# EasyEDA_schematic.net
KiCad netlist of a schematic drawn in EasyEDA
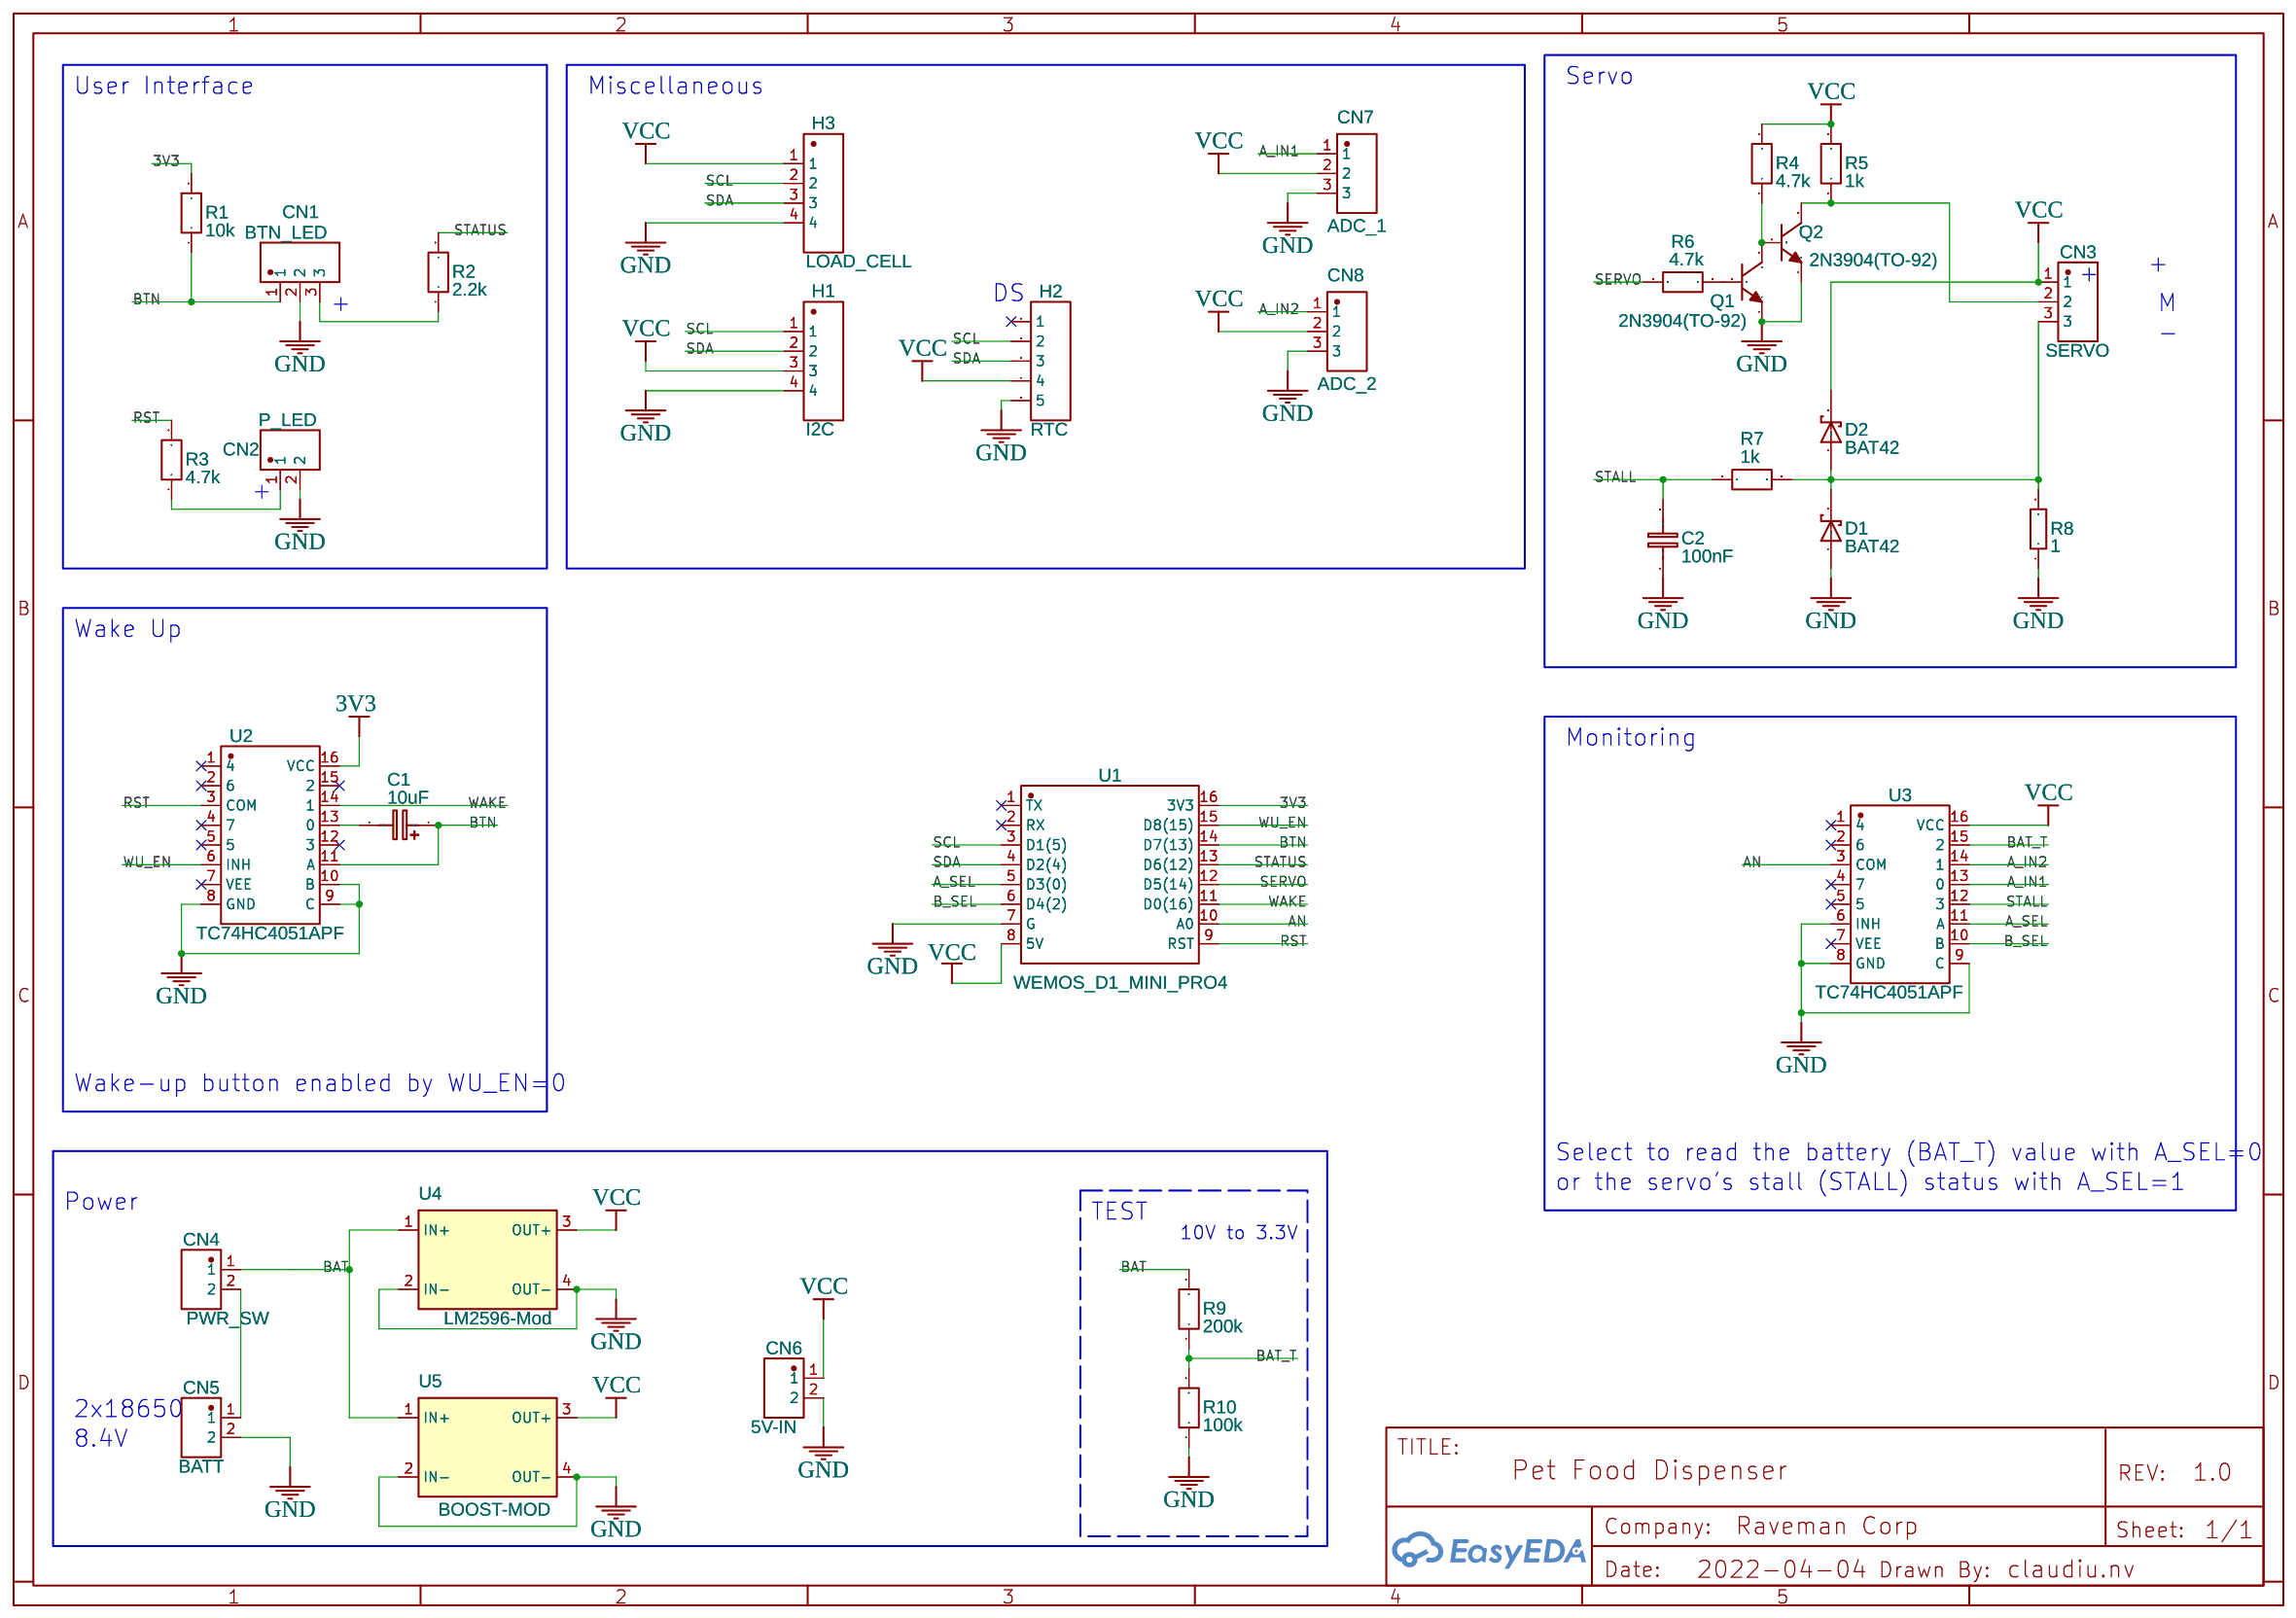
[diagram p0: schematic sheet]

(export (version "E")
  (design (tool "Eeschema 10.0.6"))
  (components
    (comp (ref "C1") (value "10uF") (libsource (lib "") (part "CE_TH_D3.0×F1.5_EU")))
    (comp (ref "C2") (value "100nF") (libsource (lib "") (part "C_RAD-0.1_EU")))
    (comp (ref "CN1")
      (value "BTN_LED")
      (fields (field (name "BOM_Manufacturer Part") "38006293") (field (name "BOM_Supplier Part") "C587424"))
      (libsource (lib "") (part "38006293_1"))
    )
    (comp (ref "CN2")
      (value "P_LED")
      (fields
        (field (name "BOM_Manufacturer Part") "1718560002")
        (field (name "BOM_Supplier Part") "C564997")
      )
      (libsource (lib "") (part "1718560002_1"))
    )
    (comp (ref "CN3")
      (value "SERVO")
      (fields (field (name "BOM_Manufacturer Part") "38006293") (field (name "BOM_Supplier Part") "C587424"))
      (libsource (lib "") (part "38006293"))
    )
    (comp (ref "CN4")
      (value "PWR_SW")
      (fields
        (field (name "BOM_Manufacturer Part") "1718560002")
        (field (name "BOM_Supplier Part") "C564997")
      )
      (libsource (lib "") (part "1718560002"))
    )
    (comp (ref "CN5")
      (value "BATT")
      (fields
        (field (name "BOM_Manufacturer Part") "1718560002")
        (field (name "BOM_Supplier Part") "C564997")
      )
      (libsource (lib "") (part "1718560002"))
    )
    (comp (ref "CN6")
      (value "5V-IN")
      (fields
        (field (name "BOM_Manufacturer Part") "1718560002")
        (field (name "BOM_Supplier Part") "C564997")
      )
      (libsource (lib "") (part "1718560002"))
    )
    (comp (ref "CN7")
      (value "ADC_1")
      (fields (field (name "BOM_Manufacturer Part") "38006293") (field (name "BOM_Supplier Part") "C587424"))
      (libsource (lib "") (part "38006293"))
    )
    (comp (ref "CN8")
      (value "ADC_2")
      (fields (field (name "BOM_Manufacturer Part") "38006293") (field (name "BOM_Supplier Part") "C587424"))
      (libsource (lib "") (part "38006293"))
    )
    (comp (ref "D1") (value "BAT42") (libsource (lib "") (part "1N5817-TP")))
    (comp (ref "D2") (value "BAT42") (libsource (lib "") (part "1N5817-TP")))
    (comp (ref "H1") (value "I2C") (libsource (lib "") (part "HEADER 4P 2.54MM")))
    (comp (ref "H2")
      (value "RTC")
      (fields (field (name "BOM_Supplier Part") "C50950"))
      (libsource (lib "") (part "HDR-F-2.54_1x5"))
    )
    (comp (ref "H3") (value "LOAD_CELL") (libsource (lib "") (part "HEADER 4P 2.54MM")))
    (comp (ref "Q1")
      (value "2N3904(TO-92)")
      (fields (field (name "BOM_Manufacturer Part") "2N3904") (field (name "BOM_Supplier Part") "C118538"))
      (libsource (lib "") (part "2N3904(TO-92)"))
    )
    (comp (ref "Q2")
      (value "2N3904(TO-92)")
      (fields (field (name "BOM_Manufacturer Part") "2N3904") (field (name "BOM_Supplier Part") "C118538"))
      (libsource (lib "") (part "2N3904(TO-92)"))
    )
    (comp (ref "R1") (value "10k") (libsource (lib "") (part "R_0603_EU")))
    (comp (ref "R2") (value "2.2k") (libsource (lib "") (part "R_0603_EU")))
    (comp (ref "R3") (value "4.7k") (libsource (lib "") (part "R_AXIAL-0.5_EU_1")))
    (comp (ref "R4") (value "4.7k") (libsource (lib "") (part "R_AXIAL-0.5_EU_1")))
    (comp (ref "R5") (value "1k") (libsource (lib "") (part "R_0603_EU")))
    (comp (ref "R6") (value "4.7k") (libsource (lib "") (part "R_0603_EU_1")))
    (comp (ref "R7") (value "1k") (libsource (lib "") (part "R_AXIAL-0.5_EU")))
    (comp (ref "R8")
      (value "1")
      (fields (field (name "BOM_Manufacturer Part") "CR-L5W1ΩJ") (field (name "BOM_Supplier Part") "C216404"))
      (libsource (lib "") (part "CR-L5W1ΩJ"))
    )
    (comp (ref "R9") (value "200k") (libsource (lib "") (part "R_AXIAL-0.5_EU_1")))
    (comp (ref "R10") (value "100k") (libsource (lib "") (part "R_AXIAL-0.5_EU_1")))
    (comp (ref "U1")
      (value "WEMOS_D1_MINI_PRO4")
      (fields
        (field (name "BOM_Manufacturer Part") "Wemos_D1_mini_Pro4")
        (field (name "BOM_Supplier Part") "C2837266")
      )
      (libsource (lib "") (part "WEMOS_D1_MINI_PRO4"))
    )
    (comp (ref "U2")
      (value "TC74HC4051APF")
      (fields (field (name "BOM_Supplier Part") "C1545945"))
      (libsource (lib "") (part "TC74HC4051APF"))
    )
    (comp (ref "U3")
      (value "TC74HC4051APF")
      (fields (field (name "BOM_Supplier Part") "C1545945"))
      (libsource (lib "") (part "TC74HC4051APF"))
    )
    (comp (ref "U4") (value "LM2596-Mod") (libsource (lib "") (part "LM2596-Mod")))
    (comp (ref "U5") (value "BOOST-MOD") (libsource (lib "") (part "BOOST-MOD")))
  )
  (nets
    (net (code "1") (name "/AN") (class "Default")
      (node (ref "U1") (pin "10") (pinfunction "A0_10") (pintype "unspecified"))
      (node (ref "U3") (pin "3") (pinfunction "COM_3") (pintype "unspecified"))
    )
    (net (code "2") (name "/A_IN1") (class "Default")
      (node (ref "CN7") (pin "1") (pinfunction "1_1") (pintype "unspecified"))
      (node (ref "U3") (pin "13") (pinfunction "0_13") (pintype "unspecified"))
    )
    (net (code "3") (name "/A_IN2") (class "Default")
      (node (ref "CN8") (pin "1") (pinfunction "1_1") (pintype "unspecified"))
      (node (ref "U3") (pin "14") (pinfunction "1_14") (pintype "unspecified"))
    )
    (net (code "4") (name "/A_SEL") (class "Default")
      (node (ref "U1") (pin "5") (pinfunction "D3(0)_5") (pintype "unspecified"))
      (node (ref "U3") (pin "11") (pinfunction "A_11") (pintype "unspecified"))
    )
    (net (code "5") (name "/BAT") (class "Default")
      (node (ref "CN4") (pin "1") (pinfunction "1_1") (pintype "unspecified"))
      (node (ref "R9") (pin "2") (pinfunction "2_2") (pintype "unspecified"))
      (node (ref "U4") (pin "1") (pinfunction "IN+_1") (pintype "passive"))
      (node (ref "U5") (pin "1") (pinfunction "IN+_1") (pintype "passive"))
    )
    (net (code "6") (name "/BAT_T") (class "Default")
      (node (ref "R10") (pin "2") (pinfunction "2_2") (pintype "unspecified"))
      (node (ref "R9") (pin "1") (pinfunction "1_1") (pintype "unspecified"))
      (node (ref "U3") (pin "15") (pinfunction "2_15") (pintype "unspecified"))
    )
    (net (code "7") (name "/BTN") (class "Default")
      (node (ref "C1") (pin "1") (pinfunction "1_1") (pintype "unspecified"))
      (node (ref "CN1") (pin "1") (pinfunction "1_1") (pintype "unspecified"))
      (node (ref "R1") (pin "1") (pinfunction "1_1") (pintype "unspecified"))
      (node (ref "U1") (pin "14") (pinfunction "D7(13)_14") (pintype "unspecified"))
      (node (ref "U2") (pin "11") (pinfunction "A_11") (pintype "unspecified"))
    )
    (net (code "8") (name "/B_SEL") (class "Default")
      (node (ref "U1") (pin "6") (pinfunction "D4(2)_6") (pintype "unspecified"))
      (node (ref "U3") (pin "10") (pinfunction "B_10") (pintype "unspecified"))
    )
    (net (code "9") (name "/RST") (class "Default")
      (node (ref "R3") (pin "2") (pinfunction "2_2") (pintype "unspecified"))
      (node (ref "U1") (pin "9") (pinfunction "RST_9") (pintype "unspecified"))
      (node (ref "U2") (pin "3") (pinfunction "COM_3") (pintype "unspecified"))
    )
    (net (code "10") (name "/SCL") (class "Default")
      (node (ref "H1") (pin "1") (pinfunction "1_1") (pintype "unspecified"))
      (node (ref "H2") (pin "2") (pinfunction "2_2") (pintype "unspecified"))
      (node (ref "H3") (pin "2") (pinfunction "2_2") (pintype "unspecified"))
      (node (ref "U1") (pin "3") (pinfunction "D1(5)_3") (pintype "unspecified"))
    )
    (net (code "11") (name "/SDA") (class "Default")
      (node (ref "H1") (pin "2") (pinfunction "2_2") (pintype "unspecified"))
      (node (ref "H2") (pin "3") (pinfunction "3_3") (pintype "unspecified"))
      (node (ref "H3") (pin "3") (pinfunction "3_3") (pintype "unspecified"))
      (node (ref "U1") (pin "4") (pinfunction "D2(4)_4") (pintype "unspecified"))
    )
    (net (code "12") (name "/SERVO") (class "Default")
      (node (ref "R6") (pin "1") (pinfunction "1_1") (pintype "unspecified"))
      (node (ref "U1") (pin "12") (pinfunction "D5(14)_12") (pintype "unspecified"))
    )
    (net (code "13") (name "/STALL") (class "Default")
      (node (ref "C2") (pin "2") (pinfunction "2_2") (pintype "unspecified"))
      (node (ref "R7") (pin "1") (pinfunction "1_1") (pintype "unspecified"))
      (node (ref "U3") (pin "12") (pinfunction "3_12") (pintype "unspecified"))
    )
    (net (code "14") (name "/STATUS") (class "Default")
      (node (ref "R2") (pin "2") (pinfunction "2_2") (pintype "unspecified"))
      (node (ref "U1") (pin "13") (pinfunction "D6(12)_13") (pintype "unspecified"))
    )
    (net (code "15") (name "/WAKE") (class "Default")
      (node (ref "U1") (pin "11") (pinfunction "D0(16)_11") (pintype "unspecified"))
      (node (ref "U2") (pin "14") (pinfunction "1_14") (pintype "unspecified"))
    )
    (net (code "16") (name "/WU_EN") (class "Default")
      (node (ref "U1") (pin "15") (pinfunction "D8(15)_15") (pintype "unspecified"))
      (node (ref "U2") (pin "6") (pinfunction "INH_6") (pintype "unspecified"))
    )
    (net (code "17") (name "3V3") (class "Default")
      (node (ref "R1") (pin "2") (pinfunction "2_2") (pintype "unspecified"))
      (node (ref "U1") (pin "16") (pinfunction "3V3_16") (pintype "unspecified"))
      (node (ref "U2") (pin "16") (pinfunction "VCC_16") (pintype "unspecified"))
    )
    (net (code "18") (name "GND") (class "Default")
      (node (ref "C2") (pin "1") (pinfunction "1_1") (pintype "unspecified"))
      (node (ref "CN1") (pin "2") (pinfunction "2_2") (pintype "unspecified"))
      (node (ref "CN2") (pin "2") (pinfunction "2_2") (pintype "unspecified"))
      (node (ref "CN5") (pin "2") (pinfunction "2_2") (pintype "unspecified"))
      (node (ref "CN6") (pin "2") (pinfunction "2_2") (pintype "unspecified"))
      (node (ref "CN7") (pin "3") (pinfunction "3_3") (pintype "unspecified"))
      (node (ref "CN8") (pin "3") (pinfunction "3_3") (pintype "unspecified"))
      (node (ref "D1") (pin "A") (pinfunction "A_A") (pintype "bidirectional"))
      (node (ref "H1") (pin "4") (pinfunction "4_4") (pintype "unspecified"))
      (node (ref "H2") (pin "5") (pinfunction "5_5") (pintype "unspecified"))
      (node (ref "H3") (pin "4") (pinfunction "4_4") (pintype "unspecified"))
      (node (ref "Q1") (pin "1") (pinfunction "E_1") (pintype "unspecified"))
      (node (ref "Q2") (pin "1") (pinfunction "E_1") (pintype "unspecified"))
      (node (ref "R10") (pin "1") (pinfunction "1_1") (pintype "unspecified"))
      (node (ref "R8") (pin "1") (pinfunction "1_1") (pintype "unspecified"))
      (node (ref "U1") (pin "7") (pinfunction "G_7") (pintype "unspecified"))
      (node (ref "U2") (pin "10") (pinfunction "B_10") (pintype "unspecified"))
      (node (ref "U2") (pin "8") (pinfunction "GND_8") (pintype "unspecified"))
      (node (ref "U2") (pin "9") (pinfunction "C_9") (pintype "unspecified"))
      (node (ref "U3") (pin "6") (pinfunction "INH_6") (pintype "unspecified"))
      (node (ref "U3") (pin "8") (pinfunction "GND_8") (pintype "unspecified"))
      (node (ref "U3") (pin "9") (pinfunction "C_9") (pintype "unspecified"))
      (node (ref "U4") (pin "2") (pinfunction "IN-_2") (pintype "passive"))
      (node (ref "U4") (pin "4") (pinfunction "OUT-_4") (pintype "passive"))
      (node (ref "U5") (pin "2") (pinfunction "IN-_2") (pintype "passive"))
      (node (ref "U5") (pin "4") (pinfunction "OUT-_4") (pintype "passive"))
    )
    (net (code "19") (name "Net-(CN1-Pad3)") (class "Default")
      (node (ref "CN1") (pin "3") (pinfunction "3_3") (pintype "unspecified"))
      (node (ref "R2") (pin "1") (pinfunction "1_1") (pintype "unspecified"))
    )
    (net (code "20") (name "Net-(CN2-Pad1)") (class "Default")
      (node (ref "CN2") (pin "1") (pinfunction "1_1") (pintype "unspecified"))
      (node (ref "R3") (pin "1") (pinfunction "1_1") (pintype "unspecified"))
    )
    (net (code "21") (name "Net-(CN3-Pad3)") (class "Default")
      (node (ref "CN3") (pin "3") (pinfunction "3_3") (pintype "unspecified"))
      (node (ref "D1") (pin "C") (pinfunction "C_C") (pintype "bidirectional"))
      (node (ref "D2") (pin "A") (pinfunction "A_A") (pintype "bidirectional"))
      (node (ref "R7") (pin "2") (pinfunction "2_2") (pintype "unspecified"))
      (node (ref "R8") (pin "2") (pinfunction "2_2") (pintype "unspecified"))
    )
    (net (code "22") (name "Net-(CN4-Pad2)") (class "Default")
      (node (ref "CN4") (pin "2") (pinfunction "2_2") (pintype "unspecified"))
      (node (ref "CN5") (pin "1") (pinfunction "1_1") (pintype "unspecified"))
    )
    (net (code "23") (name "Net-(Q1-B)") (class "Default")
      (node (ref "Q1") (pin "2") (pinfunction "B_2") (pintype "unspecified"))
      (node (ref "R6") (pin "2") (pinfunction "2_2") (pintype "unspecified"))
    )
    (net (code "24") (name "Net-(Q1-C)") (class "Default")
      (node (ref "Q1") (pin "3") (pinfunction "C_3") (pintype "unspecified"))
      (node (ref "Q2") (pin "2") (pinfunction "B_2") (pintype "unspecified"))
      (node (ref "R4") (pin "1") (pinfunction "1_1") (pintype "unspecified"))
    )
    (net (code "25") (name "Net-(Q2-C)") (class "Default")
      (node (ref "CN3") (pin "2") (pinfunction "2_2") (pintype "unspecified"))
      (node (ref "Q2") (pin "3") (pinfunction "C_3") (pintype "unspecified"))
      (node (ref "R5") (pin "1") (pinfunction "1_1") (pintype "unspecified"))
    )
    (net (code "26") (name "Net-(U2-0)") (class "Default")
      (node (ref "C1") (pin "2") (pinfunction "2_2") (pintype "unspecified"))
      (node (ref "U2") (pin "13") (pinfunction "0_13") (pintype "unspecified"))
    )
    (net (code "27") (name "VCC") (class "Default")
      (node (ref "CN3") (pin "1") (pinfunction "1_1") (pintype "unspecified"))
      (node (ref "CN6") (pin "1") (pinfunction "1_1") (pintype "unspecified"))
      (node (ref "CN7") (pin "2") (pinfunction "2_2") (pintype "unspecified"))
      (node (ref "CN8") (pin "2") (pinfunction "2_2") (pintype "unspecified"))
      (node (ref "D2") (pin "C") (pinfunction "C_C") (pintype "bidirectional"))
      (node (ref "H1") (pin "3") (pinfunction "3_3") (pintype "unspecified"))
      (node (ref "H2") (pin "4") (pinfunction "4_4") (pintype "unspecified"))
      (node (ref "H3") (pin "1") (pinfunction "1_1") (pintype "unspecified"))
      (node (ref "R4") (pin "2") (pinfunction "2_2") (pintype "unspecified"))
      (node (ref "R5") (pin "2") (pinfunction "2_2") (pintype "unspecified"))
      (node (ref "U1") (pin "8") (pinfunction "5V_8") (pintype "unspecified"))
      (node (ref "U3") (pin "16") (pinfunction "VCC_16") (pintype "unspecified"))
      (node (ref "U4") (pin "3") (pinfunction "OUT+_3") (pintype "passive"))
      (node (ref "U5") (pin "3") (pinfunction "OUT+_3") (pintype "passive"))
    )
    (net (code "28") (name "unconnected-(H2-Pad1)") (class "Default")
      (node (ref "H2") (pin "1") (pinfunction "1_1") (pintype "unspecified+no_connect"))
    )
    (net (code "29") (name "unconnected-(U1-RX-Pad2)") (class "Default")
      (node (ref "U1") (pin "2") (pinfunction "RX_2") (pintype "unspecified+no_connect"))
    )
    (net (code "30") (name "unconnected-(U1-TX-Pad1)") (class "Default")
      (node (ref "U1") (pin "1") (pinfunction "TX_1") (pintype "unspecified+no_connect"))
    )
    (net (code "31") (name "unconnected-(U2-2-Pad15)") (class "Default")
      (node (ref "U2") (pin "15") (pinfunction "2_15") (pintype "unspecified+no_connect"))
    )
    (net (code "32") (name "unconnected-(U2-3-Pad12)") (class "Default")
      (node (ref "U2") (pin "12") (pinfunction "3_12") (pintype "unspecified+no_connect"))
    )
    (net (code "33") (name "unconnected-(U2-4-Pad1)") (class "Default")
      (node (ref "U2") (pin "1") (pinfunction "4_1") (pintype "unspecified+no_connect"))
    )
    (net (code "34") (name "unconnected-(U2-6-Pad2)") (class "Default")
      (node (ref "U2") (pin "2") (pinfunction "6_2") (pintype "unspecified+no_connect"))
    )
    (net (code "35") (name "unconnected-(U2-7-Pad4)") (class "Default")
      (node (ref "U2") (pin "4") (pinfunction "7_4") (pintype "unspecified+no_connect"))
    )
    (net (code "36") (name "unconnected-(U2-Pad5)") (class "Default")
      (node (ref "U2") (pin "5") (pinfunction "5_5") (pintype "unspecified+no_connect"))
    )
    (net (code "37") (name "unconnected-(U2-VEE-Pad7)") (class "Default")
      (node (ref "U2") (pin "7") (pinfunction "VEE_7") (pintype "unspecified+no_connect"))
    )
    (net (code "38") (name "unconnected-(U3-4-Pad1)") (class "Default")
      (node (ref "U3") (pin "1") (pinfunction "4_1") (pintype "unspecified+no_connect"))
    )
    (net (code "39") (name "unconnected-(U3-6-Pad2)") (class "Default")
      (node (ref "U3") (pin "2") (pinfunction "6_2") (pintype "unspecified+no_connect"))
    )
    (net (code "40") (name "unconnected-(U3-7-Pad4)") (class "Default")
      (node (ref "U3") (pin "4") (pinfunction "7_4") (pintype "unspecified+no_connect"))
    )
    (net (code "41") (name "unconnected-(U3-Pad5)") (class "Default")
      (node (ref "U3") (pin "5") (pinfunction "5_5") (pintype "unspecified+no_connect"))
    )
    (net (code "42") (name "unconnected-(U3-VEE-Pad7)") (class "Default")
      (node (ref "U3") (pin "7") (pinfunction "VEE_7") (pintype "unspecified+no_connect"))
    )
  )
)
